# sensor_1.net
KiCad netlist of a schematic drawn in EAGLE
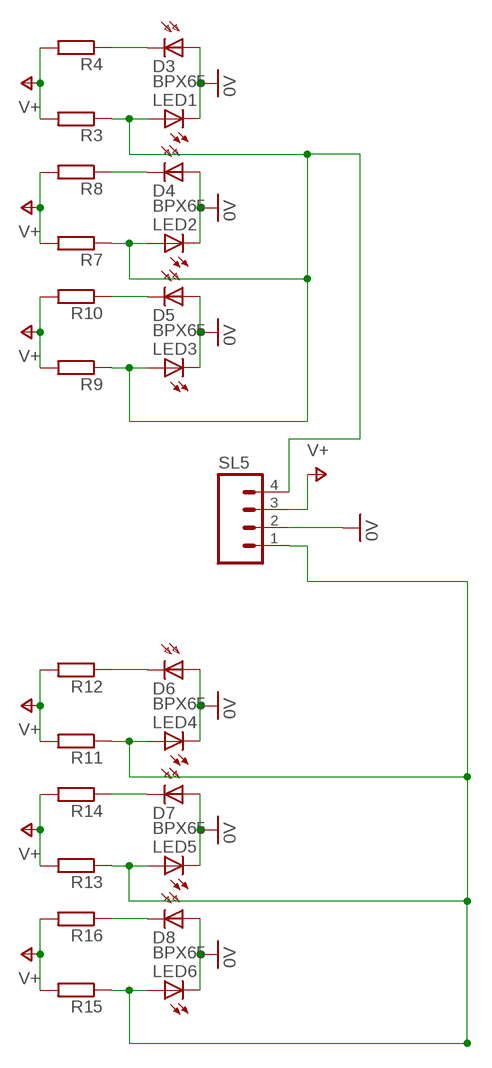
[diagram p0: schematic, sheet 1]

(export (version "E")
  (design (tool "Eeschema 10.0.6"))
  (components
    (comp (ref "D3")
      (value "BPX65")
      (footprint "eagle-import:BPX65")
      (fields (field (name "MPN") "BPX65."))
      (libsource (lib "eagle-import") (part "BPX65"))
    )
    (comp (ref "D4")
      (value "BPX65")
      (footprint "eagle-import:BPX65")
      (fields (field (name "MPN") "BPX65."))
      (libsource (lib "eagle-import") (part "BPX65"))
    )
    (comp (ref "D5")
      (value "BPX65")
      (footprint "eagle-import:BPX65")
      (fields (field (name "MPN") "BPX65."))
      (libsource (lib "eagle-import") (part "BPX65"))
    )
    (comp (ref "D6")
      (value "BPX65")
      (footprint "eagle-import:BPX65")
      (fields (field (name "MPN") "BPX65."))
      (libsource (lib "eagle-import") (part "BPX65"))
    )
    (comp (ref "D7")
      (value "BPX65")
      (footprint "eagle-import:BPX65")
      (fields (field (name "MPN") "BPX65."))
      (libsource (lib "eagle-import") (part "BPX65"))
    )
    (comp (ref "D8")
      (value "BPX65")
      (footprint "eagle-import:BPX65")
      (fields (field (name "MPN") "BPX65."))
      (libsource (lib "eagle-import") (part "BPX65"))
    )
    (comp (ref "LED1")
      (value "LED5MM")
      (footprint "eagle-import:LED5MM")
      (libsource (lib "eagle-import") (part "LED5MM"))
    )
    (comp (ref "LED2")
      (value "LED5MM")
      (footprint "eagle-import:LED5MM")
      (libsource (lib "eagle-import") (part "LED5MM"))
    )
    (comp (ref "LED3")
      (value "LED5MM")
      (footprint "eagle-import:LED5MM")
      (libsource (lib "eagle-import") (part "LED5MM"))
    )
    (comp (ref "LED4")
      (value "LED5MM")
      (footprint "eagle-import:LED5MM")
      (libsource (lib "eagle-import") (part "LED5MM"))
    )
    (comp (ref "LED5")
      (value "LED5MM")
      (footprint "eagle-import:LED5MM")
      (libsource (lib "eagle-import") (part "LED5MM"))
    )
    (comp (ref "LED6")
      (value "LED5MM")
      (footprint "eagle-import:LED5MM")
      (libsource (lib "eagle-import") (part "LED5MM"))
    )
    (comp (ref "R3")
      (value "R-EU_0204/7")
      (footprint "eagle-import:0204_7")
      (libsource (lib "eagle-import") (part "R-EU_0204/7"))
    )
    (comp (ref "R4")
      (value "R-EU_0204/7")
      (footprint "eagle-import:0204_7")
      (libsource (lib "eagle-import") (part "R-EU_0204/7"))
    )
    (comp (ref "R7")
      (value "R-EU_0204/7")
      (footprint "eagle-import:0204_7")
      (libsource (lib "eagle-import") (part "R-EU_0204/7"))
    )
    (comp (ref "R8")
      (value "R-EU_0204/7")
      (footprint "eagle-import:0204_7")
      (libsource (lib "eagle-import") (part "R-EU_0204/7"))
    )
    (comp (ref "R9")
      (value "R-EU_0204/7")
      (footprint "eagle-import:0204_7")
      (libsource (lib "eagle-import") (part "R-EU_0204/7"))
    )
    (comp (ref "R10")
      (value "R-EU_0204/7")
      (footprint "eagle-import:0204_7")
      (libsource (lib "eagle-import") (part "R-EU_0204/7"))
    )
    (comp (ref "R11")
      (value "R-EU_0204/7")
      (footprint "eagle-import:0204_7")
      (libsource (lib "eagle-import") (part "R-EU_0204/7"))
    )
    (comp (ref "R12")
      (value "R-EU_0204/7")
      (footprint "eagle-import:0204_7")
      (libsource (lib "eagle-import") (part "R-EU_0204/7"))
    )
    (comp (ref "R13")
      (value "R-EU_0204/7")
      (footprint "eagle-import:0204_7")
      (libsource (lib "eagle-import") (part "R-EU_0204/7"))
    )
    (comp (ref "R14")
      (value "R-EU_0204/7")
      (footprint "eagle-import:0204_7")
      (libsource (lib "eagle-import") (part "R-EU_0204/7"))
    )
    (comp (ref "R15")
      (value "R-EU_0204/7")
      (footprint "eagle-import:0204_7")
      (libsource (lib "eagle-import") (part "R-EU_0204/7"))
    )
    (comp (ref "R16")
      (value "R-EU_0204/7")
      (footprint "eagle-import:0204_7")
      (libsource (lib "eagle-import") (part "R-EU_0204/7"))
    )
    (comp (ref "SL5")
      (value "M04")
      (footprint "eagle-import:04P")
      (libsource (lib "eagle-import") (part "M04"))
    )
  )
  (nets
    (net (code "1") (name "0V") (class "Default")
      (node (ref "D3") (pin "A") (pinfunction "A_A") (pintype "passive"))
      (node (ref "D4") (pin "A") (pinfunction "A_A") (pintype "passive"))
      (node (ref "D5") (pin "A") (pinfunction "A_A") (pintype "passive"))
      (node (ref "D6") (pin "A") (pinfunction "A_A") (pintype "passive"))
      (node (ref "D7") (pin "A") (pinfunction "A_A") (pintype "passive"))
      (node (ref "D8") (pin "A") (pinfunction "A_A") (pintype "passive"))
      (node (ref "LED1") (pin "K") (pinfunction "C_K") (pintype "passive"))
      (node (ref "LED2") (pin "K") (pinfunction "C_K") (pintype "passive"))
      (node (ref "LED3") (pin "K") (pinfunction "C_K") (pintype "passive"))
      (node (ref "LED4") (pin "K") (pinfunction "C_K") (pintype "passive"))
      (node (ref "LED5") (pin "K") (pinfunction "C_K") (pintype "passive"))
      (node (ref "LED6") (pin "K") (pinfunction "C_K") (pintype "passive"))
      (node (ref "SL5") (pin "2") (pinfunction "2_2") (pintype "passive"))
    )
    (net (code "2") (name "Net-(D3-C)") (class "Default")
      (node (ref "D3") (pin "K") (pinfunction "C_K") (pintype "passive"))
      (node (ref "R4") (pin "1") (pinfunction "1_1") (pintype "passive"))
    )
    (net (code "3") (name "Net-(D4-C)") (class "Default")
      (node (ref "D4") (pin "K") (pinfunction "C_K") (pintype "passive"))
      (node (ref "R8") (pin "1") (pinfunction "1_1") (pintype "passive"))
    )
    (net (code "4") (name "Net-(D5-C)") (class "Default")
      (node (ref "D5") (pin "K") (pinfunction "C_K") (pintype "passive"))
      (node (ref "R10") (pin "1") (pinfunction "1_1") (pintype "passive"))
    )
    (net (code "5") (name "Net-(D6-C)") (class "Default")
      (node (ref "D6") (pin "K") (pinfunction "C_K") (pintype "passive"))
      (node (ref "R12") (pin "1") (pinfunction "1_1") (pintype "passive"))
    )
    (net (code "6") (name "Net-(D7-C)") (class "Default")
      (node (ref "D7") (pin "K") (pinfunction "C_K") (pintype "passive"))
      (node (ref "R14") (pin "1") (pinfunction "1_1") (pintype "passive"))
    )
    (net (code "7") (name "Net-(D8-C)") (class "Default")
      (node (ref "D8") (pin "K") (pinfunction "C_K") (pintype "passive"))
      (node (ref "R16") (pin "1") (pinfunction "1_1") (pintype "passive"))
    )
    (net (code "8") (name "Net-(LED1-PadA)") (class "Default")
      (node (ref "LED1") (pin "A") (pinfunction "A_A") (pintype "passive"))
      (node (ref "LED2") (pin "A") (pinfunction "A_A") (pintype "passive"))
      (node (ref "LED3") (pin "A") (pinfunction "A_A") (pintype "passive"))
      (node (ref "R3") (pin "1") (pinfunction "1_1") (pintype "passive"))
      (node (ref "R7") (pin "1") (pinfunction "1_1") (pintype "passive"))
      (node (ref "R9") (pin "1") (pinfunction "1_1") (pintype "passive"))
      (node (ref "SL5") (pin "4") (pinfunction "4_4") (pintype "passive"))
    )
    (net (code "9") (name "Net-(LED4-PadA)") (class "Default")
      (node (ref "LED4") (pin "A") (pinfunction "A_A") (pintype "passive"))
      (node (ref "LED5") (pin "A") (pinfunction "A_A") (pintype "passive"))
      (node (ref "LED6") (pin "A") (pinfunction "A_A") (pintype "passive"))
      (node (ref "R11") (pin "1") (pinfunction "1_1") (pintype "passive"))
      (node (ref "R13") (pin "1") (pinfunction "1_1") (pintype "passive"))
      (node (ref "R15") (pin "1") (pinfunction "1_1") (pintype "passive"))
      (node (ref "SL5") (pin "1") (pinfunction "1_1") (pintype "passive"))
    )
    (net (code "10") (name "V+") (class "Default")
      (node (ref "R10") (pin "2") (pinfunction "2_2") (pintype "passive"))
      (node (ref "R11") (pin "2") (pinfunction "2_2") (pintype "passive"))
      (node (ref "R12") (pin "2") (pinfunction "2_2") (pintype "passive"))
      (node (ref "R13") (pin "2") (pinfunction "2_2") (pintype "passive"))
      (node (ref "R14") (pin "2") (pinfunction "2_2") (pintype "passive"))
      (node (ref "R15") (pin "2") (pinfunction "2_2") (pintype "passive"))
      (node (ref "R16") (pin "2") (pinfunction "2_2") (pintype "passive"))
      (node (ref "R3") (pin "2") (pinfunction "2_2") (pintype "passive"))
      (node (ref "R4") (pin "2") (pinfunction "2_2") (pintype "passive"))
      (node (ref "R7") (pin "2") (pinfunction "2_2") (pintype "passive"))
      (node (ref "R8") (pin "2") (pinfunction "2_2") (pintype "passive"))
      (node (ref "R9") (pin "2") (pinfunction "2_2") (pintype "passive"))
      (node (ref "SL5") (pin "3") (pinfunction "3_3") (pintype "passive"))
    )
  )
)
